# Support.net
KiCad netlist of a schematic drawn in Altium Designer
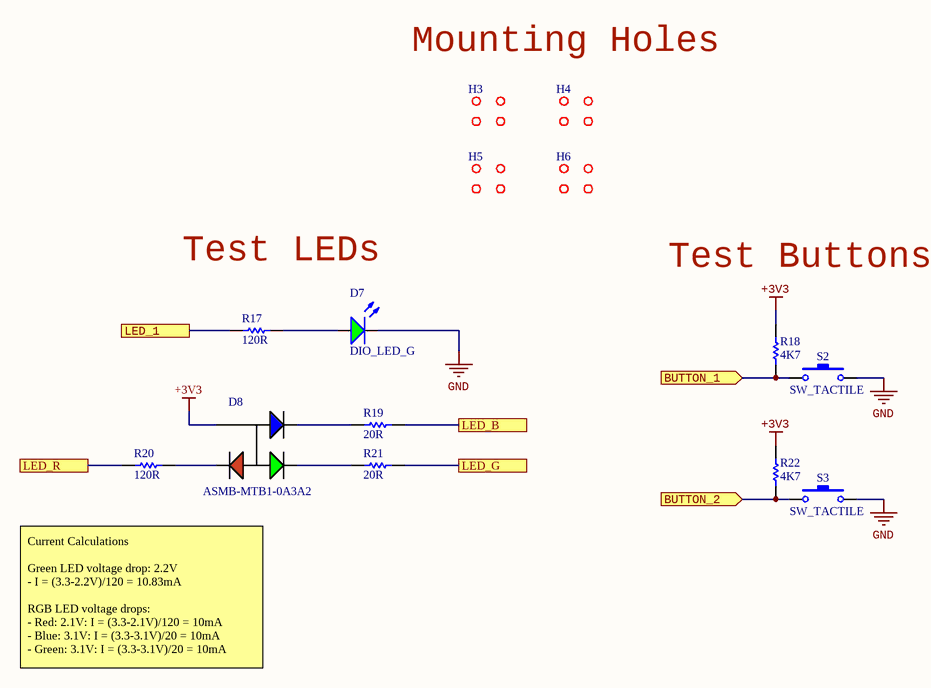
[diagram p0: Support.SchDoc]

(export (version "E")
  (design (tool "Eeschema 10.0.6"))
  (components
    (comp (ref "D7")
      (value "DIO_LED_G")
      (footprint "LED_0805_LINE")
      (description "LED GREEN DIFFUSED 0805 SMD")
      (fields (field (name "MANUFACTURER") "OSRAM") (field (name "MPN") "LG R971-KN-1"))
      (libsource (lib "UWRT_Schematic_Library_2020") (part "DIO_LED_G"))
    )
    (comp (ref "D8")
      (value "LED_RGB")
      (footprint "LED_RGB")
      (description "LED RGB DIFFUSED 4PLCC SMD")
      (fields (field (name "MANUFACTURER PART NUMBER 1") "ASMB-MTB1-0A3A2"))
      (libsource (lib "UWRT_Schematic_Library_2020") (part "LED_RGB"))
    )
    (comp (ref "H3")
      (value "MOUNTING_HOLES")
      (footprint "MOUNTING_HOLE")
      (description "6cm x 6cm")
      (libsource (lib "UWRT_Schematic_Library_2020") (part "MOUNTING_HOLES"))
    )
    (comp (ref "H4")
      (value "MOUNTING_HOLES")
      (footprint "MOUNTING_HOLE")
      (description "6cm x 6cm")
      (libsource (lib "UWRT_Schematic_Library_2020") (part "MOUNTING_HOLES"))
    )
    (comp (ref "H5")
      (value "MOUNTING_HOLES")
      (footprint "MOUNTING_HOLE")
      (description "6cm x 6cm")
      (libsource (lib "UWRT_Schematic_Library_2020") (part "MOUNTING_HOLES"))
    )
    (comp (ref "H6")
      (value "MOUNTING_HOLES")
      (footprint "MOUNTING_HOLE")
      (description "6cm x 6cm")
      (libsource (lib "UWRT_Schematic_Library_2020") (part "MOUNTING_HOLES"))
    )
    (comp (ref "R17")
      (value "120R")
      (footprint "RESC0603(1608)_N")
      (description "RES SMD 120 OHM 5% 1/10W 0603")
      (fields (field (name "MANUFACTURER") "Yageo") (field (name "TOLERANCE") "5%"))
      (libsource (lib "UWRT_Schematic_Library_2020") (part "RES_120R_0603"))
    )
    (comp (ref "R18")
      (value "4K7")
      (footprint "RESC0603(1608)_N")
      (description "RES SMD 4.7K OHM 5% 1/10W 0603")
      (fields (field (name "MANUFACTURER") "Yageo") (field (name "TOLERANCE") "5%"))
      (libsource (lib "UWRT_Schematic_Library_2020") (part "RES_4K7_0603"))
    )
    (comp (ref "R19")
      (value "20R")
      (footprint "RESC0603(1608)_N")
      (description "RES SMD 20 OHM 5% 1/10W 0603")
      (fields (field (name "MANUFACTURER") "Yageo") (field (name "MPN") "RC0603JR-0720RL"))
      (libsource (lib "UWRT_Schematic_Library_2020") (part "RES_20R_0603"))
    )
    (comp (ref "R20")
      (value "120R")
      (footprint "RESC0603(1608)_N")
      (description "RES SMD 120 OHM 5% 1/10W 0603")
      (fields (field (name "MANUFACTURER") "Yageo") (field (name "MPN") "RC0603JR-07120RL"))
      (libsource (lib "UWRT_Schematic_Library_2020") (part "RES_120R_0603"))
    )
    (comp (ref "R21")
      (value "20R")
      (footprint "RESC0603(1608)_N")
      (description "RES SMD 20 OHM 5% 1/10W 0603")
      (fields (field (name "MANUFACTURER") "Yageo") (field (name "MPN") "RC0603JR-0720RL"))
      (libsource (lib "UWRT_Schematic_Library_2020") (part "RES_20R_0603"))
    )
    (comp (ref "R22")
      (value "4K7")
      (footprint "RESC0603(1608)_N")
      (description "RES SMD 4.7K OHM 5% 1/10W 0603")
      (fields (field (name "MANUFACTURER") "Yageo") (field (name "TOLERANCE") "5%"))
      (libsource (lib "UWRT_Schematic_Library_2020") (part "RES_4K7_0603"))
    )
    (comp (ref "S2")
      (value "SW_TACTILE")
      (footprint "B3U-1100P")
      (description "Tactile Switch (Grey)")
      (fields (field (name "MPN") "B3U-1100P") (field (name "MANUFACTURER") "Omron Electronics Inc-EMC Div"))
      (libsource (lib "UWRT_Schematic_Library_2020") (part "SW_TACTILE"))
    )
    (comp (ref "S3")
      (value "SW_TACTILE")
      (footprint "B3U-1100P")
      (description "Tactile Switch (Grey)")
      (fields (field (name "MPN") "B3U-1100P") (field (name "MANUFACTURER") "Omron Electronics Inc-EMC Div"))
      (libsource (lib "UWRT_Schematic_Library_2020") (part "SW_TACTILE"))
    )
  )
  (nets
    (net (code "1") (name "+3V3") (class "Default")
      (node (ref "D8") (pin "4") (pinfunction "9_4") (pintype "passive"))
      (node (ref "R18") (pin "1") (pinfunction "1_1") (pintype "passive"))
      (node (ref "R22") (pin "2") (pinfunction "2_2") (pintype "passive"))
    )
    (net (code "2") (name "/BUTTON_1") (class "Default")
      (node (ref "R18") (pin "2") (pinfunction "2_2") (pintype "passive"))
      (node (ref "S2") (pin "1") (pinfunction "1_1") (pintype "passive"))
    )
    (net (code "3") (name "/BUTTON_2") (class "Default")
      (node (ref "R22") (pin "1") (pinfunction "1_1") (pintype "passive"))
      (node (ref "S3") (pin "1") (pinfunction "1_1") (pintype "passive"))
    )
    (net (code "4") (name "/LED_1") (class "Default")
      (node (ref "R17") (pin "1") (pinfunction "1_1") (pintype "passive"))
    )
    (net (code "5") (name "/LED_B") (class "Default")
      (node (ref "R19") (pin "2") (pinfunction "2_2") (pintype "passive"))
    )
    (net (code "6") (name "/LED_G") (class "Default")
      (node (ref "R21") (pin "2") (pinfunction "2_2") (pintype "passive"))
    )
    (net (code "7") (name "/LED_R") (class "Default")
      (node (ref "R20") (pin "1") (pinfunction "1_1") (pintype "passive"))
    )
    (net (code "8") (name "GND") (class "Default")
      (node (ref "D7") (pin "2") (pinfunction "K_2") (pintype "passive"))
      (node (ref "S2") (pin "2") (pinfunction "2_2") (pintype "passive"))
      (node (ref "S3") (pin "2") (pinfunction "2_2") (pintype "passive"))
    )
    (net (code "9") (name "Net-(D7-A)") (class "Default")
      (node (ref "D7") (pin "1") (pinfunction "A_1") (pintype "passive"))
      (node (ref "R17") (pin "2") (pinfunction "2_2") (pintype "passive"))
    )
    (net (code "10") (name "Net-(D8-10)") (class "Default")
      (node (ref "D8") (pin "3") (pinfunction "10_3") (pintype "passive"))
      (node (ref "R19") (pin "1") (pinfunction "1_1") (pintype "passive"))
    )
    (net (code "11") (name "Net-(D8-11)") (class "Default")
      (node (ref "D8") (pin "1") (pinfunction "11_1") (pintype "passive"))
      (node (ref "R20") (pin "2") (pinfunction "2_2") (pintype "passive"))
    )
    (net (code "12") (name "Net-(D8-12)") (class "Default")
      (node (ref "D8") (pin "2") (pinfunction "12_2") (pintype "passive"))
      (node (ref "R21") (pin "1") (pinfunction "1_1") (pintype "passive"))
    )
  )
)
